# Filter_L.net
KiCad netlist of a schematic drawn in Altium Designer
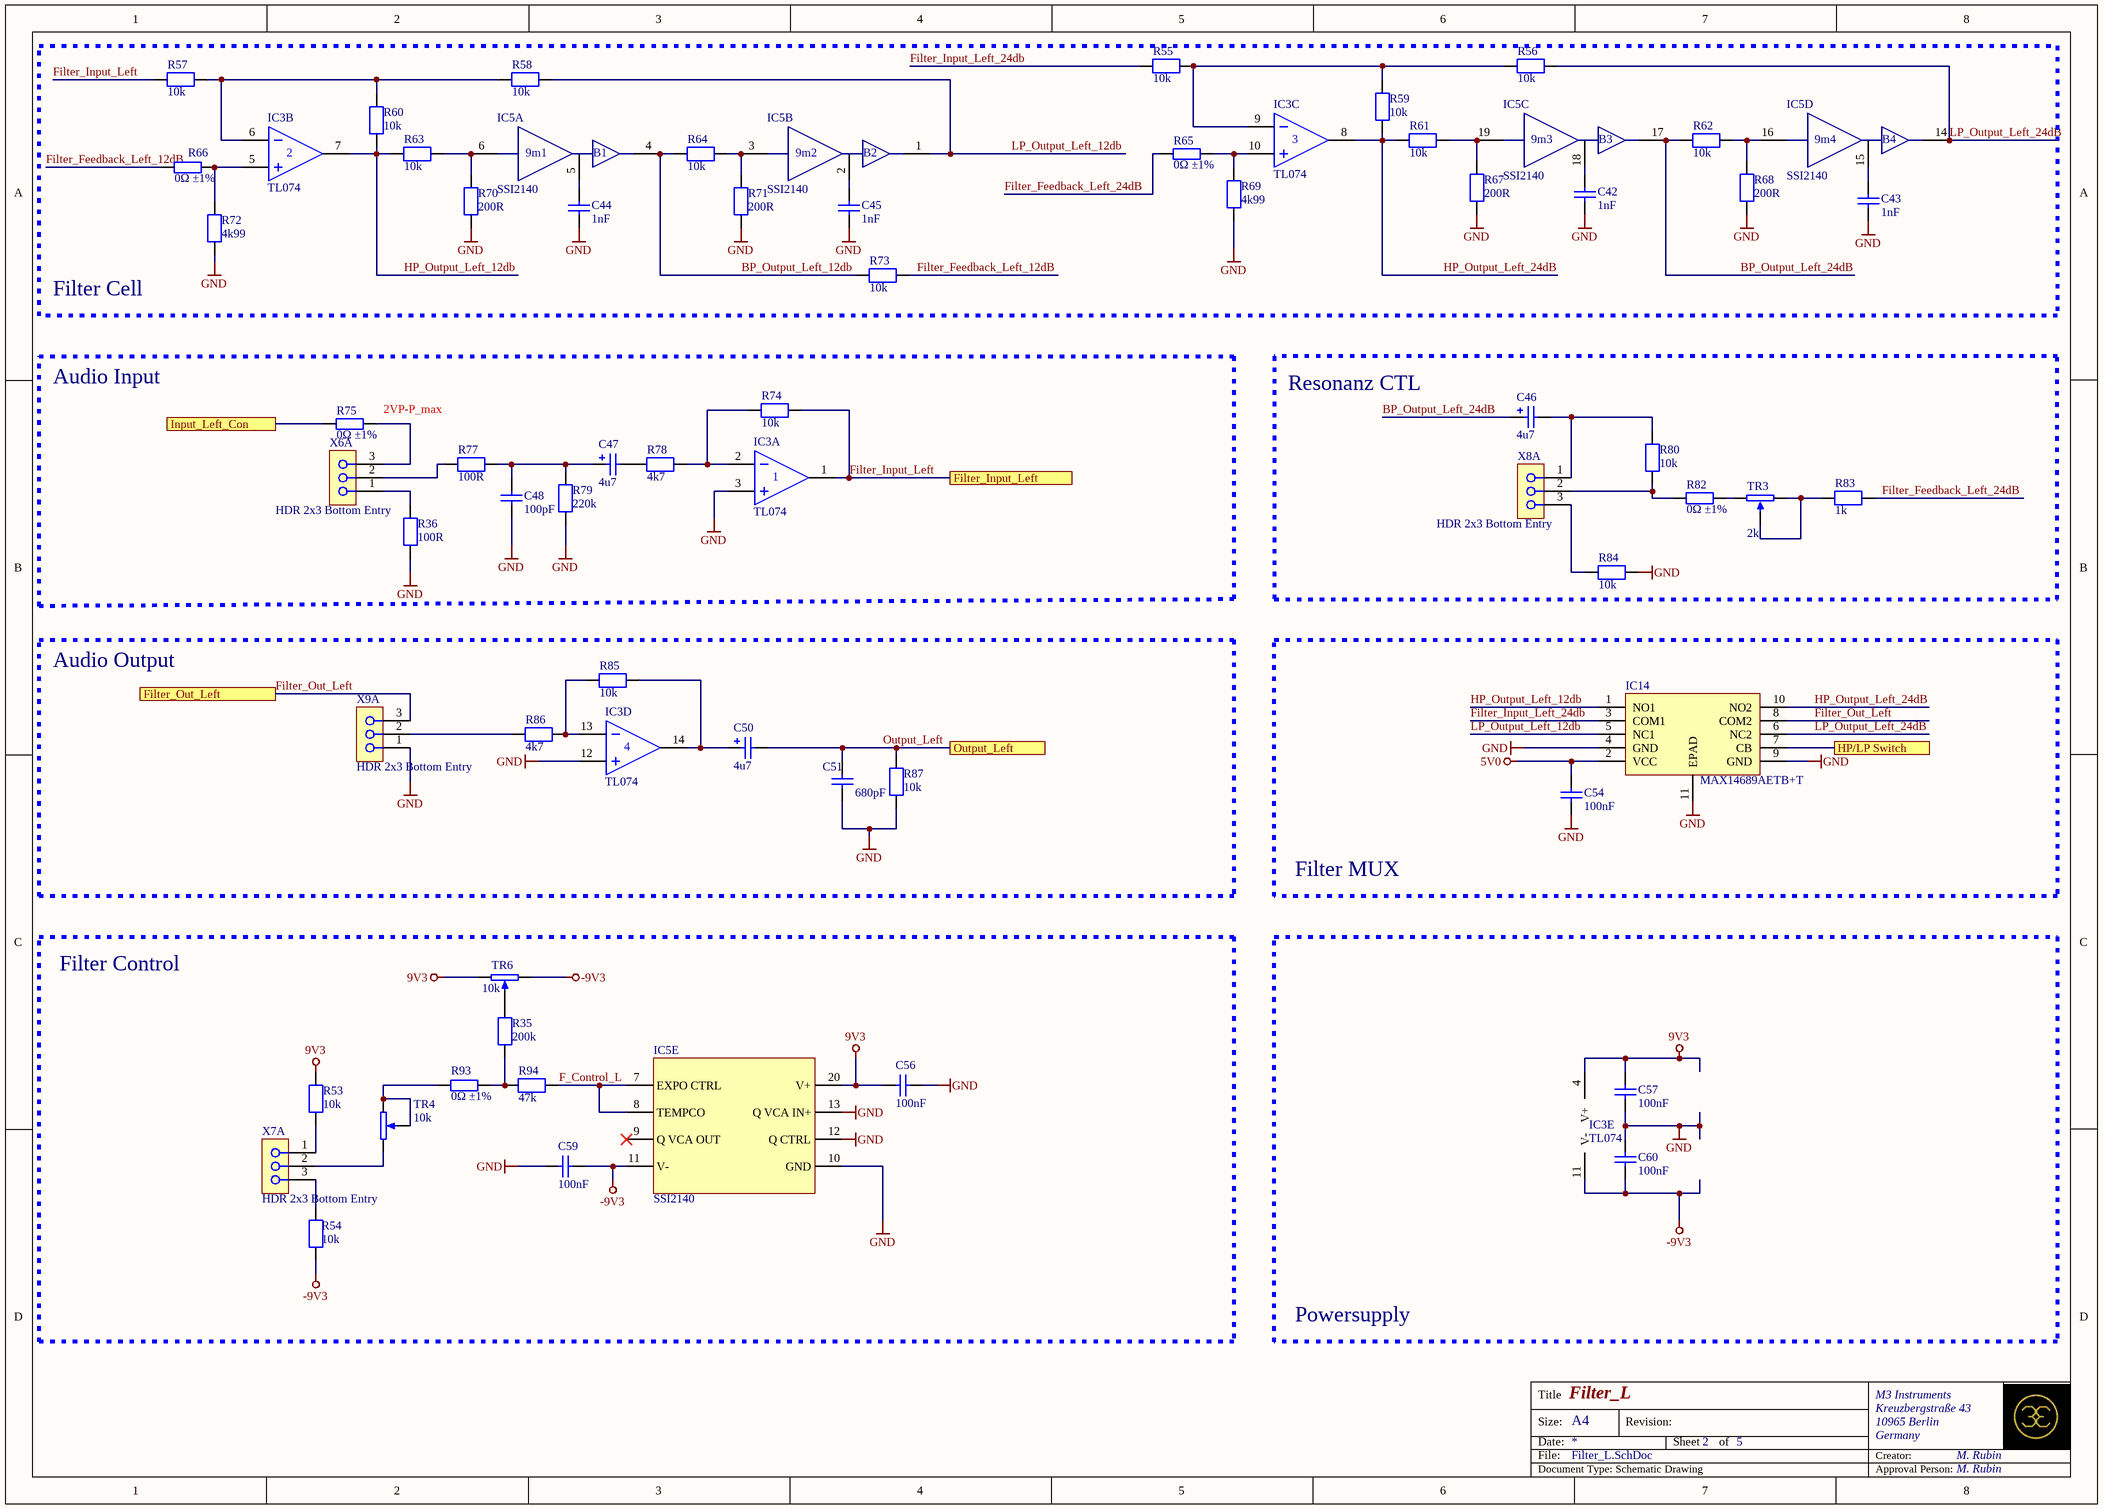
[diagram p0: Filter_L.SchDoc]

(export (version "E")
  (design (tool "Eeschema 10.0.6"))
  (components
    (comp (ref "C42")
      (value "1nF")
      (footprint "CAPC2012X145N")
      (description "Multilayer Ceramic Capacitors MLCC - SMD/SMT, C0G(NP0), 100nF")
      (fields
        (field (name "MANUFACTURER") "Murata Electronics")
        (field (name "MANUFACTURER PART NUMBER") "GRM21B5C2J102JWA3L")
      )
      (libsource (lib "Caps") (part "CAP_1nF_630V"))
    )
    (comp (ref "C43")
      (value "1nF")
      (footprint "CAPC2012X145N")
      (description "Multilayer Ceramic Capacitors MLCC - SMD/SMT, C0G(NP0), 1nF")
      (fields
        (field (name "MANUFACTURER") "Murata Electronics")
        (field (name "MANUFACTURER PART NUMBER") "GRM21B5C2J102JWA3L")
      )
      (libsource (lib "Caps") (part "CAP_100nF_630V"))
    )
    (comp (ref "C44")
      (value "1nF")
      (footprint "CAPC2012X145N")
      (description "Multilayer Ceramic Capacitors MLCC - SMD/SMT, C0G(NP0), 100nF")
      (fields
        (field (name "MANUFACTURER") "Murata Electronics")
        (field (name "MANUFACTURER PART NUMBER") "GRM21B5C2J102JWA3L")
      )
      (libsource (lib "Caps") (part "CAP_1nF_630V"))
    )
    (comp (ref "C45")
      (value "1nF")
      (footprint "CAPC2012X145N")
      (description "Multilayer Ceramic Capacitors MLCC - SMD/SMT, C0G(NP0), 1nF")
      (fields
        (field (name "MANUFACTURER") "Murata Electronics")
        (field (name "MANUFACTURER PART NUMBER") "GRM21B5C2J102JWA3L")
      )
      (libsource (lib "Caps") (part "CAP_100nF_630V"))
    )
    (comp (ref "C46")
      (value "4u7")
      (footprint "CAPAE4643X54M")
      (description "Aluminium Electrolytic Capacitors - SMD 4.7UF 16V ELECT VS BI-POLAR")
      (fields
        (field (name "MANUFACTURER") "Panasonic")
        (field (name "MANUFACTURER PART NUMBER") "EEE-1CA4R7NR")
      )
      (libsource (lib "Caps") (part "CAP_4u7"))
    )
    (comp (ref "C47")
      (value "4u7")
      (footprint "CAPAE4643X54M")
      (description "Aluminium Electrolytic Capacitors - SMD 4.7UF 16V ELECT VS BI-POLAR")
      (fields
        (field (name "MANUFACTURER") "Panasonic")
        (field (name "MANUFACTURER PART NUMBER") "EEE-1CA4R7NR")
      )
      (libsource (lib "Caps") (part "CAP_4u7"))
    )
    (comp (ref "C48")
      (value "100pF")
      (footprint "CAPC2012X145N")
      (description "Film Capacitors 100pF 50VDC 2% PPS FILM 0805")
      (fields
        (field (name "MANUFACTURER") "Panasonic")
        (field (name "MANUFACTURER PART NUMBER") "ECH-U1H101GX5")
      )
      (libsource (lib "Caps") (part "CAP_100pF_0805"))
    )
    (comp (ref "C50")
      (value "4u7")
      (footprint "CAPAE4643X54M")
      (description "Aluminium Electrolytic Capacitors - SMD 4.7UF 16V ELECT VS BI-POLAR")
      (fields
        (field (name "MANUFACTURER") "Panasonic")
        (field (name "MANUFACTURER PART NUMBER") "EEE-1CA4R7NR")
      )
      (libsource (lib "Caps") (part "CAP_4u7"))
    )
    (comp (ref "C51")
      (value "680pF")
      (footprint "CAPC2012X145N")
      (description "Film Capacitors 680pF 50VDC 2% PPS FILM 0805")
      (fields
        (field (name "MANUFACTURER") "Panasonic")
        (field (name "MANUFACTURER PART NUMBER") "ECH-U1H681GX5")
      )
      (libsource (lib "Caps") (part "CAP_680pF_0805"))
    )
    (comp (ref "C54")
      (value "100nF")
      (footprint "CAPC1608X95N")
      (description "Multilayer Ceramic Capacitors MLCC - SMD/SMT, 100nF")
      (fields
        (field (name "MANUFACTURER") "YAGEO")
        (field (name "MANUFACTURER PART NUMBER") "CC0603KRX7R9BB104")
      )
      (libsource (lib "Caps") (part "CAP_100nF_0603"))
    )
    (comp (ref "C56")
      (value "100nF")
      (footprint "CAPC1608X95N")
      (description "Multilayer Ceramic Capacitors MLCC - SMD/SMT, 100nF")
      (fields
        (field (name "MANUFACTURER") "YAGEO")
        (field (name "MANUFACTURER PART NUMBER") "CC0603KRX7R9BB104")
      )
      (libsource (lib "Caps") (part "CAP_100nF_0603"))
    )
    (comp (ref "C57")
      (value "100nF")
      (footprint "CAPC1608X95N")
      (description "Multilayer Ceramic Capacitors MLCC - SMD/SMT, 100nF")
      (fields
        (field (name "MANUFACTURER") "YAGEO")
        (field (name "MANUFACTURER PART NUMBER") "CC0603KRX7R9BB104")
      )
      (libsource (lib "Caps") (part "CAP_100nF_0603"))
    )
    (comp (ref "C59")
      (value "100nF")
      (footprint "CAPC1608X95N")
      (description "Multilayer Ceramic Capacitors MLCC - SMD/SMT, 100nF")
      (fields
        (field (name "MANUFACTURER") "YAGEO")
        (field (name "MANUFACTURER PART NUMBER") "CC0603KRX7R9BB104")
      )
      (libsource (lib "Caps") (part "CAP_100nF_0603"))
    )
    (comp (ref "C60")
      (value "100nF")
      (footprint "CAPC1608X95N")
      (description "Multilayer Ceramic Capacitors MLCC - SMD/SMT, 100nF")
      (fields
        (field (name "MANUFACTURER") "YAGEO")
        (field (name "MANUFACTURER PART NUMBER") "CC0603KRX7R9BB104")
      )
      (libsource (lib "Caps") (part "CAP_100nF_0603"))
    )
    (comp (ref "IC3")
      (value "TL074")
      (footprint "SOIC127P600X175-14N")
      (description "Operational Amplifiers - Op Amps Dual JFET Op Amp")
      (fields
        (field (name "MANUFACTURER") "Texas Instruments")
        (field (name "MANUFACTURER PART NUMBER") "TL074CDR")
      )
      (libsource (lib "ICs") (part "IC_TL074"))
    )
    (comp (ref "IC5")
      (value "SSI2140")
      (footprint "SOP65P650-20N")
      (description "Voltage Controlled Multi-Mode Filter")
      (fields (field (name "MANUFACTURER") "Sound Semiconductor"))
      (libsource (lib "ICs") (part "IC_SSI2140"))
    )
    (comp (ref "IC14")
      (value "MAX14689AETB+T")
      (footprint "QFN40P200X250X80_HS-11N")
      (description "Analogue Switch ICs Ultra-Small, Low-RON, Beyond-the-Rails™, DPDT Analog Switches")
      (fields (field (name "MANUFACTURER") "Maxim Integrated"))
      (libsource (lib "ICs") (part "IC_MAX14689AETB+T"))
    )
    (comp (ref "R35")
      (value "200k")
      (footprint "RESC2012X70N")
      (description "Thick Film Resistors - SMD 1/8watt 200Kohms 1%")
      (fields
        (field (name "MANUFACTURER") "Vishay / Dale")
        (field (name "MANUFACTURER PART NUMBER") "CRCW0805200KFKEA")
      )
      (libsource (lib "Resistors") (part "RES_200k_0805"))
    )
    (comp (ref "R36")
      (value "100R")
      (footprint "RESC2012X70N")
      (description "Thick Film Resistors 1/8watt 100ohms 1% 100ppm")
      (fields
        (field (name "MANUFACTURER") "Vishay / Dale")
        (field (name "MANUFACTURER PART NUMBER") "CRCW0805100RFKEA")
      )
      (libsource (lib "Resistors") (part "RES_100R_0805"))
    )
    (comp (ref "R53")
      (value "10k")
      (footprint "RESC2012X70N")
      (description "Thick Film Resistors - SMD 1/8watt 10Kohms 1% 100ppm")
      (fields
        (field (name "MANUFACTURER") "Vishay / Dale")
        (field (name "MANUFACTURER PART NUMBER") "CRCW080510K0FKEA")
      )
      (libsource (lib "Resistors") (part "RES_10k_0805"))
    )
    (comp (ref "R54")
      (value "10k")
      (footprint "RESC2012X70N")
      (description "Thick Film Resistors - SMD 1/8watt 10Kohms 1% 100ppm")
      (fields (field (name "TOLERANCE") "1%") (field (name "MANUFACTURER PART NUMBER") "CRCW080510K0FKEA"))
      (libsource (lib "Resistors") (part "RES_10k_0805"))
    )
    (comp (ref "R55")
      (value "10k")
      (footprint "RESC2012X70N")
      (description "Thick Film Resistors - SMD 1/8watt 10Kohms 1% 100ppm")
      (fields
        (field (name "MANUFACTURER") "Vishay / Dale")
        (field (name "MANUFACTURER PART NUMBER") "CRCW080510K0FKEA")
      )
      (libsource (lib "") (part "RES_10k_0805_2"))
    )
    (comp (ref "R56")
      (value "10k")
      (footprint "RESC2012X70N")
      (description "Thick Film Resistors - SMD 1/8watt 10Kohms 1% 100ppm")
      (fields
        (field (name "MANUFACTURER") "Vishay / Dale")
        (field (name "MANUFACTURER PART NUMBER") "CRCW080510K0FKEA")
      )
      (libsource (lib "") (part "RES_10k_0805_1"))
    )
    (comp (ref "R57")
      (value "10k")
      (footprint "RESC2012X70N")
      (description "Thick Film Resistors - SMD 1/8watt 10Kohms 1% 100ppm")
      (fields
        (field (name "MANUFACTURER") "Vishay / Dale")
        (field (name "MANUFACTURER PART NUMBER") "CRCW080510K0FKEA")
      )
      (libsource (lib "") (part "RES_10k_0805_1"))
    )
    (comp (ref "R58")
      (value "10k")
      (footprint "RESC2012X70N")
      (description "Thick Film Resistors - SMD 1/8watt 10Kohms 1% 100ppm")
      (fields
        (field (name "MANUFACTURER") "Vishay / Dale")
        (field (name "MANUFACTURER PART NUMBER") "CRCW080510K0FKEA")
      )
      (libsource (lib "") (part "RES_10k_0805_1"))
    )
    (comp (ref "R59")
      (value "10k")
      (footprint "RESC2012X70N")
      (description "Thick Film Resistors - SMD 1/8watt 10Kohms 1% 100ppm")
      (fields
        (field (name "MANUFACTURER") "Vishay / Dale")
        (field (name "MANUFACTURER PART NUMBER") "CRCW080510K0FKEA")
      )
      (libsource (lib "Resistors") (part "RES_10k_0805"))
    )
    (comp (ref "R60")
      (value "10k")
      (footprint "RESC2012X70N")
      (description "Thick Film Resistors - SMD 1/8watt 10Kohms 1% 100ppm")
      (fields
        (field (name "MANUFACTURER") "Vishay / Dale")
        (field (name "MANUFACTURER PART NUMBER") "CRCW080510K0FKEA")
      )
      (libsource (lib "Resistors") (part "RES_10k_0805"))
    )
    (comp (ref "R61")
      (value "10k")
      (footprint "RESC2012X70N")
      (description "Thick Film Resistors - SMD 1/8watt 10Kohms 1% 100ppm")
      (fields
        (field (name "MANUFACTURER") "Vishay / Dale")
        (field (name "MANUFACTURER PART NUMBER") "CRCW080510K0FKEA")
      )
      (libsource (lib "") (part "RES_10k_0805_1"))
    )
    (comp (ref "R62")
      (value "10k")
      (footprint "RESC2012X70N")
      (description "Thick Film Resistors - SMD 1/8watt 10Kohms 1% 100ppm")
      (fields
        (field (name "MANUFACTURER") "Vishay / Dale")
        (field (name "MANUFACTURER PART NUMBER") "CRCW080510K0FKEA")
      )
      (libsource (lib "") (part "RES_10k_0805_1"))
    )
    (comp (ref "R63")
      (value "10k")
      (footprint "RESC2012X70N")
      (description "Thick Film Resistors - SMD 1/8watt 10Kohms 1% 100ppm")
      (fields
        (field (name "MANUFACTURER") "Vishay / Dale")
        (field (name "MANUFACTURER PART NUMBER") "CRCW080510K0FKEA")
      )
      (libsource (lib "") (part "RES_10k_0805_1"))
    )
    (comp (ref "R64")
      (value "10k")
      (footprint "RESC2012X70N")
      (description "Thick Film Resistors - SMD 1/8watt 10Kohms 1% 100ppm")
      (fields
        (field (name "MANUFACTURER") "Vishay / Dale")
        (field (name "MANUFACTURER PART NUMBER") "CRCW080510K0FKEA")
      )
      (libsource (lib "") (part "RES_10k_0805_1"))
    )
    (comp (ref "R65")
      (value "0Ω ±1%")
      (footprint "RESC2012X70N")
      (description "Chip resistor")
      (fields (field (name "TOLERANCE") "1%") (field (name "MANUFACTURER PART NUMBER") "CRCW08050000Z0EAC"))
      (libsource (lib "Resistors") (part "0805 0R (0R0) 1%"))
    )
    (comp (ref "R66")
      (value "0Ω ±1%")
      (footprint "RESC2012X70N")
      (description "Chip resistor")
      (fields (field (name "TOLERANCE") "1%") (field (name "MANUFACTURER PART NUMBER") "CRCW08050000Z0EAC"))
      (libsource (lib "Resistors") (part "0805 0R (0R0) 1%"))
    )
    (comp (ref "R67")
      (value "200R")
      (footprint "RESC2012X70N")
      (description "Thick Film Resistors - SMD 1/8watt 200ohms 1% 100ppm")
      (fields
        (field (name "MANUFACTURER") "Vishay / Dale")
        (field (name "MANUFACTURER PART NUMBER") "CRCW0805200RFKEA")
      )
      (libsource (lib "Resistors") (part "RES_200R_0805"))
    )
    (comp (ref "R68")
      (value "200R")
      (footprint "RESC2012X70N")
      (description "Thick Film Resistors - SMD 1/8watt 200ohms 1% 100ppm")
      (fields
        (field (name "MANUFACTURER") "Vishay / Dale")
        (field (name "MANUFACTURER PART NUMBER") "CRCW0805200RFKEA")
      )
      (libsource (lib "Resistors") (part "RES_200R_0805"))
    )
    (comp (ref "R69")
      (value "4k99")
      (footprint "RESC2012X70N")
      (description "Thick Film Resistors - SMD 1/8watt 4.99Kohms 1% 100ppm")
      (fields
        (field (name "MANUFACTURER") "Vishay / Dale")
        (field (name "MANUFACTURER PART NUMBER") "CRCW08054K99FKEA")
      )
      (libsource (lib "Resistors") (part "RES_4k99_0805"))
    )
    (comp (ref "R70")
      (value "200R")
      (footprint "RESC2012X70N")
      (description "Thick Film Resistors - SMD 1/8watt 200ohms 1% 100ppm")
      (fields
        (field (name "MANUFACTURER") "Vishay / Dale")
        (field (name "MANUFACTURER PART NUMBER") "CRCW0805200RFKEA")
      )
      (libsource (lib "Resistors") (part "RES_200R_0805"))
    )
    (comp (ref "R71")
      (value "200R")
      (footprint "RESC2012X70N")
      (description "Thick Film Resistors - SMD 1/8watt 200ohms 1% 100ppm")
      (fields
        (field (name "MANUFACTURER") "Vishay / Dale")
        (field (name "MANUFACTURER PART NUMBER") "CRCW0805200RFKEA")
      )
      (libsource (lib "Resistors") (part "RES_200R_0805"))
    )
    (comp (ref "R72")
      (value "4k99")
      (footprint "RESC2012X70N")
      (description "Thick Film Resistors - SMD 1/8watt 4.99Kohms 1% 100ppm")
      (fields
        (field (name "MANUFACTURER") "Vishay / Dale")
        (field (name "MANUFACTURER PART NUMBER") "CRCW08054K99FKEA")
      )
      (libsource (lib "Resistors") (part "RES_4k99_0805"))
    )
    (comp (ref "R73")
      (value "10k")
      (footprint "RESC2012X70N")
      (description "Thick Film Resistors - SMD 1/8watt 10Kohms 1% 100ppm")
      (fields
        (field (name "MANUFACTURER") "Vishay / Dale")
        (field (name "MANUFACTURER PART NUMBER") "CRCW080510K0FKEA")
      )
      (libsource (lib "") (part "RES_10k_0805_1"))
    )
    (comp (ref "R74")
      (value "10k")
      (footprint "RESC2012X70N")
      (description "Thick Film Resistors - SMD 1/8watt 10Kohms 1% 100ppm")
      (fields
        (field (name "MANUFACTURER") "Vishay / Dale")
        (field (name "MANUFACTURER PART NUMBER") "CRCW080510K0FKEA")
      )
      (libsource (lib "") (part "RES_10k_0805_2"))
    )
    (comp (ref "R75")
      (value "0Ω ±1%")
      (footprint "RESC2012X70N")
      (description "Chip resistor")
      (fields (field (name "TOLERANCE") "1%") (field (name "MANUFACTURER PART NUMBER") "CRCW08050000Z0EAC"))
      (libsource (lib "Resistors") (part "0805 0R (0R0) 1%"))
    )
    (comp (ref "R77")
      (value "100R")
      (footprint "RESC2012X70N")
      (description "Thick Film Resistors 1/8watt 100ohms 1% 100ppm")
      (fields
        (field (name "MANUFACTURER") "Vishay / Dale")
        (field (name "MANUFACTURER PART NUMBER") "CRCW0805100RFKEA")
      )
      (libsource (lib "") (part "RES_100R_0805_1"))
    )
    (comp (ref "R78")
      (value "4k7")
      (footprint "RESC2012X70N")
      (description "Thick Film Resistors - SMD 1/8Watt 4.7Kohms 1% Commercial Use")
      (fields
        (field (name "MANUFACTURER") "Vishay / Dale")
        (field (name "MANUFACTURER PART NUMBER") "CRCW08054K70FKEAC")
      )
      (libsource (lib "Resistors") (part "RES_4k7_0805"))
    )
    (comp (ref "R79")
      (value "220k")
      (footprint "RESC2012X70N")
      (description "Thick Film Resistors - SMD 1/8watt 220Kohms 1%")
      (fields
        (field (name "MANUFACTURER") "Vishay / Dale")
        (field (name "MANUFACTURER PART NUMBER") "CRCW0805220KFKEA")
      )
      (libsource (lib "Resistors") (part "RES_220k_0805"))
    )
    (comp (ref "R80")
      (value "10k")
      (footprint "RESC2012X70N")
      (description "Thick Film Resistors - SMD 1/8watt 10Kohms 1% 100ppm")
      (fields
        (field (name "MANUFACTURER") "Vishay / Dale")
        (field (name "MANUFACTURER PART NUMBER") "CRCW080510K0FKEA")
      )
      (libsource (lib "Resistors") (part "RES_10k_0805"))
    )
    (comp (ref "R82")
      (value "0Ω ±1%")
      (footprint "RESC2012X70N")
      (description "Chip resistor")
      (fields (field (name "TOLERANCE") "1%") (field (name "MANUFACTURER PART NUMBER") "CRCW08050000Z0EAC"))
      (libsource (lib "Resistors") (part "0805 0R (0R0) 1%"))
    )
    (comp (ref "R83")
      (value "1k")
      (footprint "RESC2012X70N")
      (description "Thick Film Resistors - SMD 1/8watt 1Kohms 1% 100ppm")
      (fields
        (field (name "MANUFACTURER") "Vishay / Dale")
        (field (name "MANUFACTURER PART NUMBER") "CRCW08051K00FKEA")
      )
      (libsource (lib "Resistors") (part "RES_1k_0805"))
    )
    (comp (ref "R84")
      (value "10k")
      (footprint "RESC2012X70N")
      (description "Thick Film Resistors - SMD 1/8watt 10Kohms 1% 100ppm")
      (fields (field (name "TOLERANCE") "1%") (field (name "MANUFACTURER PART NUMBER") "CRCW080510K0FKEA"))
      (libsource (lib "") (part "RES_10k_0805_1"))
    )
    (comp (ref "R85")
      (value "10k")
      (footprint "RESC2012X70N")
      (description "Thick Film Resistors - SMD 1/8watt 10Kohms 1% 100ppm")
      (fields
        (field (name "MANUFACTURER") "Vishay / Dale")
        (field (name "MANUFACTURER PART NUMBER") "CRCW080510K0FKEA")
      )
      (libsource (lib "") (part "RES_10k_0805_2"))
    )
    (comp (ref "R86")
      (value "4k7")
      (footprint "RESC2012X70N")
      (description "Thick Film Resistors - SMD 1/8Watt 4.7Kohms 1% Commercial Use")
      (fields
        (field (name "MANUFACTURER") "Vishay / Dale")
        (field (name "MANUFACTURER PART NUMBER") "CRCW08054K70FKEAC")
      )
      (libsource (lib "Resistors") (part "RES_4k7_0805"))
    )
    (comp (ref "R87")
      (value "10k")
      (footprint "RESC2012X70N")
      (description "Thick Film Resistors - SMD 1/8watt 10Kohms 1% 100ppm")
      (fields
        (field (name "MANUFACTURER") "Vishay / Dale")
        (field (name "MANUFACTURER PART NUMBER") "CRCW080510K0FKEA")
      )
      (libsource (lib "Resistors") (part "RES_10k_0805"))
    )
    (comp (ref "R93")
      (value "0Ω ±1%")
      (footprint "RESC2012X70N")
      (description "Chip resistor")
      (fields (field (name "TOLERANCE") "1%") (field (name "MANUFACTURER PART NUMBER") "CRCW08050000Z0EAC"))
      (libsource (lib "Resistors") (part "0805 0R (0R0) 1%"))
    )
    (comp (ref "R94")
      (value "47k")
      (footprint "RESC2012X70N")
      (description "Thick Film Resistors - SMD 1/8watt 47Kohms 1%")
      (fields
        (field (name "MANUFACTURER") "Vishay / Dale")
        (field (name "MANUFACTURER PART NUMBER") "CRCW080547K0FKEB")
      )
      (libsource (lib "Resistors") (part "RES_47k_0805"))
    )
    (comp (ref "TR3")
      (value "2k")
      (footprint "PVG3G503C01R00")
      (description "Trimmer Resistors - SMD 2.0Kohms Sealed 3mm Sngl turn")
      (fields
        (field (name "MANUFACTURER") "Bourns")
        (field (name "MANUFACTURER PART NUMBER") "PVG3A202C01R00")
      )
      (libsource (lib "Resistors") (part "TRIM_2k_lin"))
    )
    (comp (ref "TR4")
      (value "10k")
      (footprint "3296Y")
      (description "10 kOhms 0.5W, 1/2W PC Pins Through Hole Trimmer Potentiometer Cermet 25.0 Turn Top Adjustment")
      (fields
        (field (name "MANUFACTURER") "Bourns")
        (field (name "MANUFACTURER PART NUMBER") "3296Y-1-103LF")
      )
      (libsource (lib "") (part "TRIM_10k_lin_25_1"))
    )
    (comp (ref "TR6")
      (value "10k")
      (footprint "3296Y")
      (description "10 kOhms 0.5W, 1/2W PC Pins Through Hole Trimmer Potentiometer Cermet 25.0 Turn Top Adjustment")
      (fields
        (field (name "MANUFACTURER") "Bourns")
        (field (name "MANUFACTURER PART NUMBER") "3296Y-1-103LF")
      )
      (libsource (lib "Resistors") (part "TRIM_10k_lin_25"))
    )
    (comp (ref "X6")
      (value "HDR 2x3 Bottom Entry")
      (footprint "613006216921-poti")
      (fields (field (name "MANUFACTURER") "WE") (field (name "MANUFACTURER PART NUMBER") "613004216921"))
      (libsource (lib "Connectors") (part "CON_SOCKET_2x3_Poti"))
    )
    (comp (ref "X7")
      (value "HDR 2x3 Bottom Entry")
      (footprint "613006216921-poti")
      (fields (field (name "MANUFACTURER") "WE") (field (name "MANUFACTURER PART NUMBER") "613004216921"))
      (libsource (lib "") (part "CON_SOCKET_2x3_Poti_1"))
    )
    (comp (ref "X8")
      (value "HDR 2x3 Bottom Entry")
      (footprint "613006216921-poti")
      (fields (field (name "MANUFACTURER") "WE") (field (name "MANUFACTURER PART NUMBER") "613004216921"))
      (libsource (lib "") (part "CON_SOCKET_2x3_Poti_1"))
    )
    (comp (ref "X9")
      (value "HDR 2x3 Bottom Entry")
      (footprint "613006216921-poti")
      (fields (field (name "MANUFACTURER") "WE") (field (name "MANUFACTURER PART NUMBER") "613004216921"))
      (libsource (lib "Connectors") (part "CON_SOCKET_2x3_Poti"))
    )
  )
  (nets
    (net (code "1") (name "-9V3") (class "Default")
      (node (ref "C59") (pin "2") (pinfunction "2_2") (pintype "passive"))
      (node (ref "C60") (pin "1") (pinfunction "1_1") (pintype "passive"))
      (node (ref "IC3") (pin "11") (pinfunction "V-_11") (pintype "power_in"))
      (node (ref "IC5") (pin "11") (pinfunction "V-_11") (pintype "passive"))
      (node (ref "R54") (pin "1") (pinfunction "1_1") (pintype "passive"))
      (node (ref "TR6") (pin "3") (pinfunction "3_3") (pintype "passive"))
    )
    (net (code "2") (name "/BP_Output_Left_12db") (class "Default")
      (node (ref "IC5") (pin "4") (pinfunction "OUT_1_4") (pintype "passive"))
      (node (ref "R64") (pin "1") (pinfunction "1_1") (pintype "passive"))
      (node (ref "R73") (pin "1") (pinfunction "1_1") (pintype "passive"))
    )
    (net (code "3") (name "/BP_Output_Left_24dB") (class "Default")
      (node (ref "C46") (pin "1") (pinfunction "1_1") (pintype "passive"))
      (node (ref "IC5") (pin "17") (pinfunction "OUT_3_17") (pintype "passive"))
      (node (ref "R62") (pin "1") (pinfunction "1_1") (pintype "passive"))
    )
    (net (code "4") (name "/F_Control_L") (class "Default")
      (node (ref "IC5") (pin "7") (pinfunction "EXPO_CTRL_7") (pintype "passive"))
      (node (ref "IC5") (pin "8") (pinfunction "TEMPCO_8") (pintype "power_in"))
      (node (ref "R94") (pin "2") (pinfunction "2_2") (pintype "passive"))
    )
    (net (code "5") (name "/Filter_Feedback_Left_12dB") (class "Default")
      (node (ref "R66") (pin "1") (pinfunction "1_1") (pintype "passive"))
      (node (ref "R73") (pin "2") (pinfunction "2_2") (pintype "passive"))
    )
    (net (code "6") (name "/Filter_Feedback_Left_24dB") (class "Default")
      (node (ref "R65") (pin "1") (pinfunction "1_1") (pintype "passive"))
      (node (ref "R83") (pin "1") (pinfunction "1_1") (pintype "passive"))
    )
    (net (code "7") (name "/Filter_Input_Left") (class "Default")
      (node (ref "IC3") (pin "1") (pinfunction "OUT_1") (pintype "passive"))
      (node (ref "R57") (pin "1") (pinfunction "1_1") (pintype "passive"))
      (node (ref "R74") (pin "1") (pinfunction "1_1") (pintype "passive"))
    )
    (net (code "8") (name "/Filter_Input_Left_24db") (class "Default")
      (node (ref "IC14") (pin "3") (pinfunction "COM1_3") (pintype "passive"))
      (node (ref "R55") (pin "2") (pinfunction "2_2") (pintype "passive"))
    )
    (net (code "9") (name "/Filter_Out_Left") (class "Default")
      (node (ref "IC14") (pin "8") (pinfunction "COM2_8") (pintype "passive"))
      (node (ref "X9") (pin "3") (pinfunction "3_3") (pintype "passive"))
    )
    (net (code "10") (name "/HP_Output_Left_12db") (class "Default")
      (node (ref "IC14") (pin "1") (pinfunction "NO1_1") (pintype "passive"))
      (node (ref "IC3") (pin "7") (pinfunction "OUT_7") (pintype "passive"))
      (node (ref "R60") (pin "1") (pinfunction "1_1") (pintype "passive"))
      (node (ref "R63") (pin "1") (pinfunction "1_1") (pintype "passive"))
    )
    (net (code "11") (name "/HP_Output_Left_24dB") (class "Default")
      (node (ref "IC14") (pin "10") (pinfunction "NO2_10") (pintype "passive"))
      (node (ref "IC3") (pin "8") (pinfunction "OUT_8") (pintype "passive"))
      (node (ref "R59") (pin "1") (pinfunction "1_1") (pintype "passive"))
      (node (ref "R61") (pin "1") (pinfunction "1_1") (pintype "passive"))
    )
    (net (code "12") (name "/HP{slash}LP Switch") (class "Default")
      (node (ref "IC14") (pin "7") (pinfunction "CB_7") (pintype "passive"))
    )
    (net (code "13") (name "/Input_Left_Con") (class "Default")
      (node (ref "R75") (pin "1") (pinfunction "1_1") (pintype "passive"))
    )
    (net (code "14") (name "/LP_Output_Left_12db") (class "Default")
      (node (ref "IC14") (pin "5") (pinfunction "NC1_5") (pintype "passive"))
      (node (ref "IC5") (pin "1") (pinfunction "OUT_2_1") (pintype "passive"))
      (node (ref "R58") (pin "2") (pinfunction "2_2") (pintype "passive"))
    )
    (net (code "15") (name "/LP_Output_Left_24dB") (class "Default")
      (node (ref "IC14") (pin "6") (pinfunction "NC2_6") (pintype "passive"))
      (node (ref "IC5") (pin "14") (pinfunction "OUT_4_14") (pintype "passive"))
      (node (ref "R56") (pin "2") (pinfunction "2_2") (pintype "passive"))
    )
    (net (code "16") (name "/Output_Left") (class "Default")
      (node (ref "C50") (pin "2") (pinfunction "2_2") (pintype "passive"))
      (node (ref "C51") (pin "2") (pinfunction "2_2") (pintype "passive"))
      (node (ref "R87") (pin "2") (pinfunction "2_2") (pintype "passive"))
    )
    (net (code "17") (name "5V0") (class "Default")
      (node (ref "C54") (pin "2") (pinfunction "2_2") (pintype "passive"))
      (node (ref "IC14") (pin "2") (pinfunction "VCC_2") (pintype "passive"))
    )
    (net (code "18") (name "9V3") (class "Default")
      (node (ref "C56") (pin "1") (pinfunction "1_1") (pintype "passive"))
      (node (ref "C57") (pin "2") (pinfunction "2_2") (pintype "passive"))
      (node (ref "IC3") (pin "4") (pinfunction "V+_4") (pintype "power_in"))
      (node (ref "IC5") (pin "20") (pinfunction "V+_20") (pintype "passive"))
      (node (ref "R53") (pin "2") (pinfunction "2_2") (pintype "passive"))
      (node (ref "TR6") (pin "1") (pinfunction "1_1") (pintype "passive"))
    )
    (net (code "19") (name "GND") (class "Default")
      (node (ref "C42") (pin "1") (pinfunction "1_1") (pintype "passive"))
      (node (ref "C43") (pin "1") (pinfunction "1_1") (pintype "passive"))
      (node (ref "C44") (pin "1") (pinfunction "1_1") (pintype "passive"))
      (node (ref "C45") (pin "1") (pinfunction "1_1") (pintype "passive"))
      (node (ref "C48") (pin "1") (pinfunction "1_1") (pintype "passive"))
      (node (ref "C51") (pin "1") (pinfunction "1_1") (pintype "passive"))
      (node (ref "C54") (pin "1") (pinfunction "1_1") (pintype "passive"))
      (node (ref "C56") (pin "2") (pinfunction "2_2") (pintype "passive"))
      (node (ref "C57") (pin "1") (pinfunction "1_1") (pintype "passive"))
      (node (ref "C59") (pin "1") (pinfunction "1_1") (pintype "passive"))
      (node (ref "C60") (pin "2") (pinfunction "2_2") (pintype "passive"))
      (node (ref "IC14") (pin "11") (pinfunction "EPAD_11") (pintype "passive"))
      (node (ref "IC14") (pin "4") (pinfunction "GND_4") (pintype "passive"))
      (node (ref "IC14") (pin "9") (pinfunction "GND_9") (pintype "passive"))
      (node (ref "IC3") (pin "12") (pinfunction "IN+_12") (pintype "passive"))
      (node (ref "IC3") (pin "3") (pinfunction "IN+_3") (pintype "passive"))
      (node (ref "IC5") (pin "10") (pinfunction "GND_10") (pintype "passive"))
      (node (ref "IC5") (pin "12") (pinfunction "Q_CTRL_12") (pintype "power_in"))
      (node (ref "IC5") (pin "13") (pinfunction "Q_VCA_IN+_13") (pintype "power_in"))
      (node (ref "R36") (pin "1") (pinfunction "1_1") (pintype "passive"))
      (node (ref "R67") (pin "1") (pinfunction "1_1") (pintype "passive"))
      (node (ref "R68") (pin "1") (pinfunction "1_1") (pintype "passive"))
      (node (ref "R69") (pin "1") (pinfunction "1_1") (pintype "passive"))
      (node (ref "R70") (pin "1") (pinfunction "1_1") (pintype "passive"))
      (node (ref "R71") (pin "1") (pinfunction "1_1") (pintype "passive"))
      (node (ref "R72") (pin "1") (pinfunction "1_1") (pintype "passive"))
      (node (ref "R79") (pin "1") (pinfunction "1_1") (pintype "passive"))
      (node (ref "R84") (pin "2") (pinfunction "2_2") (pintype "passive"))
      (node (ref "R87") (pin "1") (pinfunction "1_1") (pintype "passive"))
      (node (ref "X9") (pin "1") (pinfunction "1_1") (pintype "passive"))
    )
    (net (code "20") (name "Net-(C46-Pad2)") (class "Default")
      (node (ref "C46") (pin "2") (pinfunction "2_2") (pintype "passive"))
      (node (ref "R80") (pin "2") (pinfunction "2_2") (pintype "passive"))
      (node (ref "X8") (pin "1") (pinfunction "1_1") (pintype "passive"))
    )
    (net (code "21") (name "Net-(C47-Pad1)") (class "Default")
      (node (ref "C47") (pin "1") (pinfunction "1_1") (pintype "passive"))
      (node (ref "C48") (pin "2") (pinfunction "2_2") (pintype "passive"))
      (node (ref "R77") (pin "2") (pinfunction "2_2") (pintype "passive"))
      (node (ref "R79") (pin "2") (pinfunction "2_2") (pintype "passive"))
    )
    (net (code "22") (name "Net-(C47-Pad2)") (class "Default")
      (node (ref "C47") (pin "2") (pinfunction "2_2") (pintype "passive"))
      (node (ref "R78") (pin "2") (pinfunction "2_2") (pintype "passive"))
    )
    (net (code "23") (name "Net-(IC3A-IN-)") (class "Default")
      (node (ref "IC3") (pin "2") (pinfunction "IN-_2") (pintype "passive"))
      (node (ref "R74") (pin "2") (pinfunction "2_2") (pintype "passive"))
      (node (ref "R78") (pin "1") (pinfunction "1_1") (pintype "passive"))
    )
    (net (code "24") (name "Net-(IC3B-IN+)") (class "Default")
      (node (ref "IC3") (pin "5") (pinfunction "IN+_5") (pintype "passive"))
      (node (ref "R66") (pin "2") (pinfunction "2_2") (pintype "passive"))
      (node (ref "R72") (pin "2") (pinfunction "2_2") (pintype "passive"))
    )
    (net (code "25") (name "Net-(IC3B-IN-)") (class "Default")
      (node (ref "IC3") (pin "6") (pinfunction "IN-_6") (pintype "passive"))
      (node (ref "R57") (pin "2") (pinfunction "2_2") (pintype "passive"))
      (node (ref "R58") (pin "1") (pinfunction "1_1") (pintype "passive"))
      (node (ref "R60") (pin "2") (pinfunction "2_2") (pintype "passive"))
    )
    (net (code "26") (name "Net-(IC3C-IN+)") (class "Default")
      (node (ref "IC3") (pin "9") (pinfunction "IN+_9") (pintype "passive"))
      (node (ref "R55") (pin "1") (pinfunction "1_1") (pintype "passive"))
      (node (ref "R56") (pin "1") (pinfunction "1_1") (pintype "passive"))
      (node (ref "R59") (pin "2") (pinfunction "2_2") (pintype "passive"))
    )
    (net (code "27") (name "Net-(IC3C-IN-)") (class "Default")
      (node (ref "IC3") (pin "10") (pinfunction "IN-_10") (pintype "passive"))
      (node (ref "R65") (pin "2") (pinfunction "2_2") (pintype "passive"))
      (node (ref "R69") (pin "2") (pinfunction "2_2") (pintype "passive"))
    )
    (net (code "28") (name "Net-(IC3D-IN-)") (class "Default")
      (node (ref "IC3") (pin "13") (pinfunction "IN-_13") (pintype "passive"))
      (node (ref "R85") (pin "2") (pinfunction "2_2") (pintype "passive"))
      (node (ref "R86") (pin "1") (pinfunction "1_1") (pintype "passive"))
    )
    (net (code "29") (name "Net-(IC3D-OUT)") (class "Default")
      (node (ref "C50") (pin "1") (pinfunction "1_1") (pintype "passive"))
      (node (ref "IC3") (pin "14") (pinfunction "OUT_14") (pintype "passive"))
      (node (ref "R85") (pin "1") (pinfunction "1_1") (pintype "passive"))
    )
    (net (code "30") (name "Net-(IC5A-CAP_1)") (class "Default")
      (node (ref "C44") (pin "2") (pinfunction "2_2") (pintype "passive"))
      (node (ref "IC5") (pin "5") (pinfunction "CAP_1_5") (pintype "passive"))
    )
    (net (code "31") (name "Net-(IC5A-IN_1)") (class "Default")
      (node (ref "IC5") (pin "6") (pinfunction "IN_1_6") (pintype "passive"))
      (node (ref "R63") (pin "2") (pinfunction "2_2") (pintype "passive"))
      (node (ref "R70") (pin "2") (pinfunction "2_2") (pintype "passive"))
    )
    (net (code "32") (name "Net-(IC5B-CAP_2)") (class "Default")
      (node (ref "C45") (pin "2") (pinfunction "2_2") (pintype "passive"))
      (node (ref "IC5") (pin "2") (pinfunction "CAP_2_2") (pintype "power_in"))
    )
    (net (code "33") (name "Net-(IC5B-IN_2)") (class "Default")
      (node (ref "IC5") (pin "3") (pinfunction "IN_2_3") (pintype "power_in"))
      (node (ref "R64") (pin "2") (pinfunction "2_2") (pintype "passive"))
      (node (ref "R71") (pin "2") (pinfunction "2_2") (pintype "passive"))
    )
    (net (code "34") (name "Net-(IC5C-CAP_3)") (class "Default")
      (node (ref "C42") (pin "2") (pinfunction "2_2") (pintype "passive"))
      (node (ref "IC5") (pin "18") (pinfunction "CAP_3_18") (pintype "power_in"))
    )
    (net (code "35") (name "Net-(IC5C-IN_3)") (class "Default")
      (node (ref "IC5") (pin "19") (pinfunction "IN_3_19") (pintype "passive"))
      (node (ref "R61") (pin "2") (pinfunction "2_2") (pintype "passive"))
      (node (ref "R67") (pin "2") (pinfunction "2_2") (pintype "passive"))
    )
    (net (code "36") (name "Net-(IC5D-CAP_4)") (class "Default")
      (node (ref "C43") (pin "2") (pinfunction "2_2") (pintype "passive"))
      (node (ref "IC5") (pin "15") (pinfunction "CAP_4_15") (pintype "passive"))
    )
    (net (code "37") (name "Net-(IC5D-IN_4)") (class "Default")
      (node (ref "IC5") (pin "16") (pinfunction "IN_4_16") (pintype "passive"))
      (node (ref "R62") (pin "2") (pinfunction "2_2") (pintype "passive"))
      (node (ref "R68") (pin "2") (pinfunction "2_2") (pintype "passive"))
    )
    (net (code "38") (name "Net-(R35-Pad1)") (class "Default")
      (node (ref "R35") (pin "1") (pinfunction "1_1") (pintype "passive"))
      (node (ref "R93") (pin "2") (pinfunction "2_2") (pintype "passive"))
      (node (ref "R94") (pin "1") (pinfunction "1_1") (pintype "passive"))
    )
    (net (code "39") (name "Net-(R35-Pad2)") (class "Default")
      (node (ref "R35") (pin "2") (pinfunction "2_2") (pintype "passive"))
      (node (ref "TR6") (pin "2") (pinfunction "2_2") (pintype "passive"))
    )
    (net (code "40") (name "Net-(R36-Pad2)") (class "Default")
      (node (ref "R36") (pin "2") (pinfunction "2_2") (pintype "passive"))
      (node (ref "X6") (pin "1") (pinfunction "1_1") (pintype "passive"))
    )
    (net (code "41") (name "Net-(R53-Pad1)") (class "Default")
      (node (ref "R53") (pin "1") (pinfunction "1_1") (pintype "passive"))
      (node (ref "X7") (pin "1") (pinfunction "1_1") (pintype "passive"))
    )
    (net (code "42") (name "Net-(R54-Pad2)") (class "Default")
      (node (ref "R54") (pin "2") (pinfunction "2_2") (pintype "passive"))
      (node (ref "X7") (pin "3") (pinfunction "3_3") (pintype "passive"))
    )
    (net (code "43") (name "Net-(R75-Pad2)") (class "Default")
      (node (ref "R75") (pin "2") (pinfunction "2_2") (pintype "passive"))
      (node (ref "X6") (pin "3") (pinfunction "3_3") (pintype "passive"))
    )
    (net (code "44") (name "Net-(R77-Pad1)") (class "Default")
      (node (ref "R77") (pin "1") (pinfunction "1_1") (pintype "passive"))
      (node (ref "X6") (pin "2") (pinfunction "2_2") (pintype "passive"))
    )
    (net (code "45") (name "Net-(R80-Pad1)") (class "Default")
      (node (ref "R80") (pin "1") (pinfunction "1_1") (pintype "passive"))
      (node (ref "R82") (pin "1") (pinfunction "1_1") (pintype "passive"))
      (node (ref "X8") (pin "2") (pinfunction "2_2") (pintype "passive"))
    )
    (net (code "46") (name "Net-(R82-Pad2)") (class "Default")
      (node (ref "R82") (pin "2") (pinfunction "2_2") (pintype "passive"))
      (node (ref "TR3") (pin "1") (pinfunction "1_1") (pintype "passive"))
    )
    (net (code "47") (name "Net-(R83-Pad2)") (class "Default")
      (node (ref "R83") (pin "2") (pinfunction "2_2") (pintype "passive"))
      (node (ref "TR3") (pin "2") (pinfunction "2_2") (pintype "passive"))
      (node (ref "TR3") (pin "3") (pinfunction "3_3") (pintype "passive"))
    )
    (net (code "48") (name "Net-(R84-Pad1)") (class "Default")
      (node (ref "R84") (pin "1") (pinfunction "1_1") (pintype "passive"))
      (node (ref "X8") (pin "3") (pinfunction "3_3") (pintype "passive"))
    )
    (net (code "49") (name "Net-(R86-Pad2)") (class "Default")
      (node (ref "R86") (pin "2") (pinfunction "2_2") (pintype "passive"))
      (node (ref "X9") (pin "2") (pinfunction "2_2") (pintype "passive"))
    )
    (net (code "50") (name "Net-(R93-Pad1)") (class "Default")
      (node (ref "R93") (pin "1") (pinfunction "1_1") (pintype "passive"))
      (node (ref "TR4") (pin "2") (pinfunction "2_2") (pintype "passive"))
      (node (ref "TR4") (pin "3") (pinfunction "3_3") (pintype "passive"))
    )
    (net (code "51") (name "Net-(TR4-Pad1)") (class "Default")
      (node (ref "TR4") (pin "1") (pinfunction "1_1") (pintype "passive"))
      (node (ref "X7") (pin "2") (pinfunction "2_2") (pintype "passive"))
    )
    (net (code "52") (name "unconnected-(IC5E-Q_VCA_OUT-Pad9)") (class "Default")
      (node (ref "IC5") (pin "9") (pinfunction "Q_VCA_OUT_9") (pintype "passive+no_connect"))
    )
  )
)
